# TRV_CC110x_V0_2.net
KiCad netlist of a schematic drawn in EAGLE
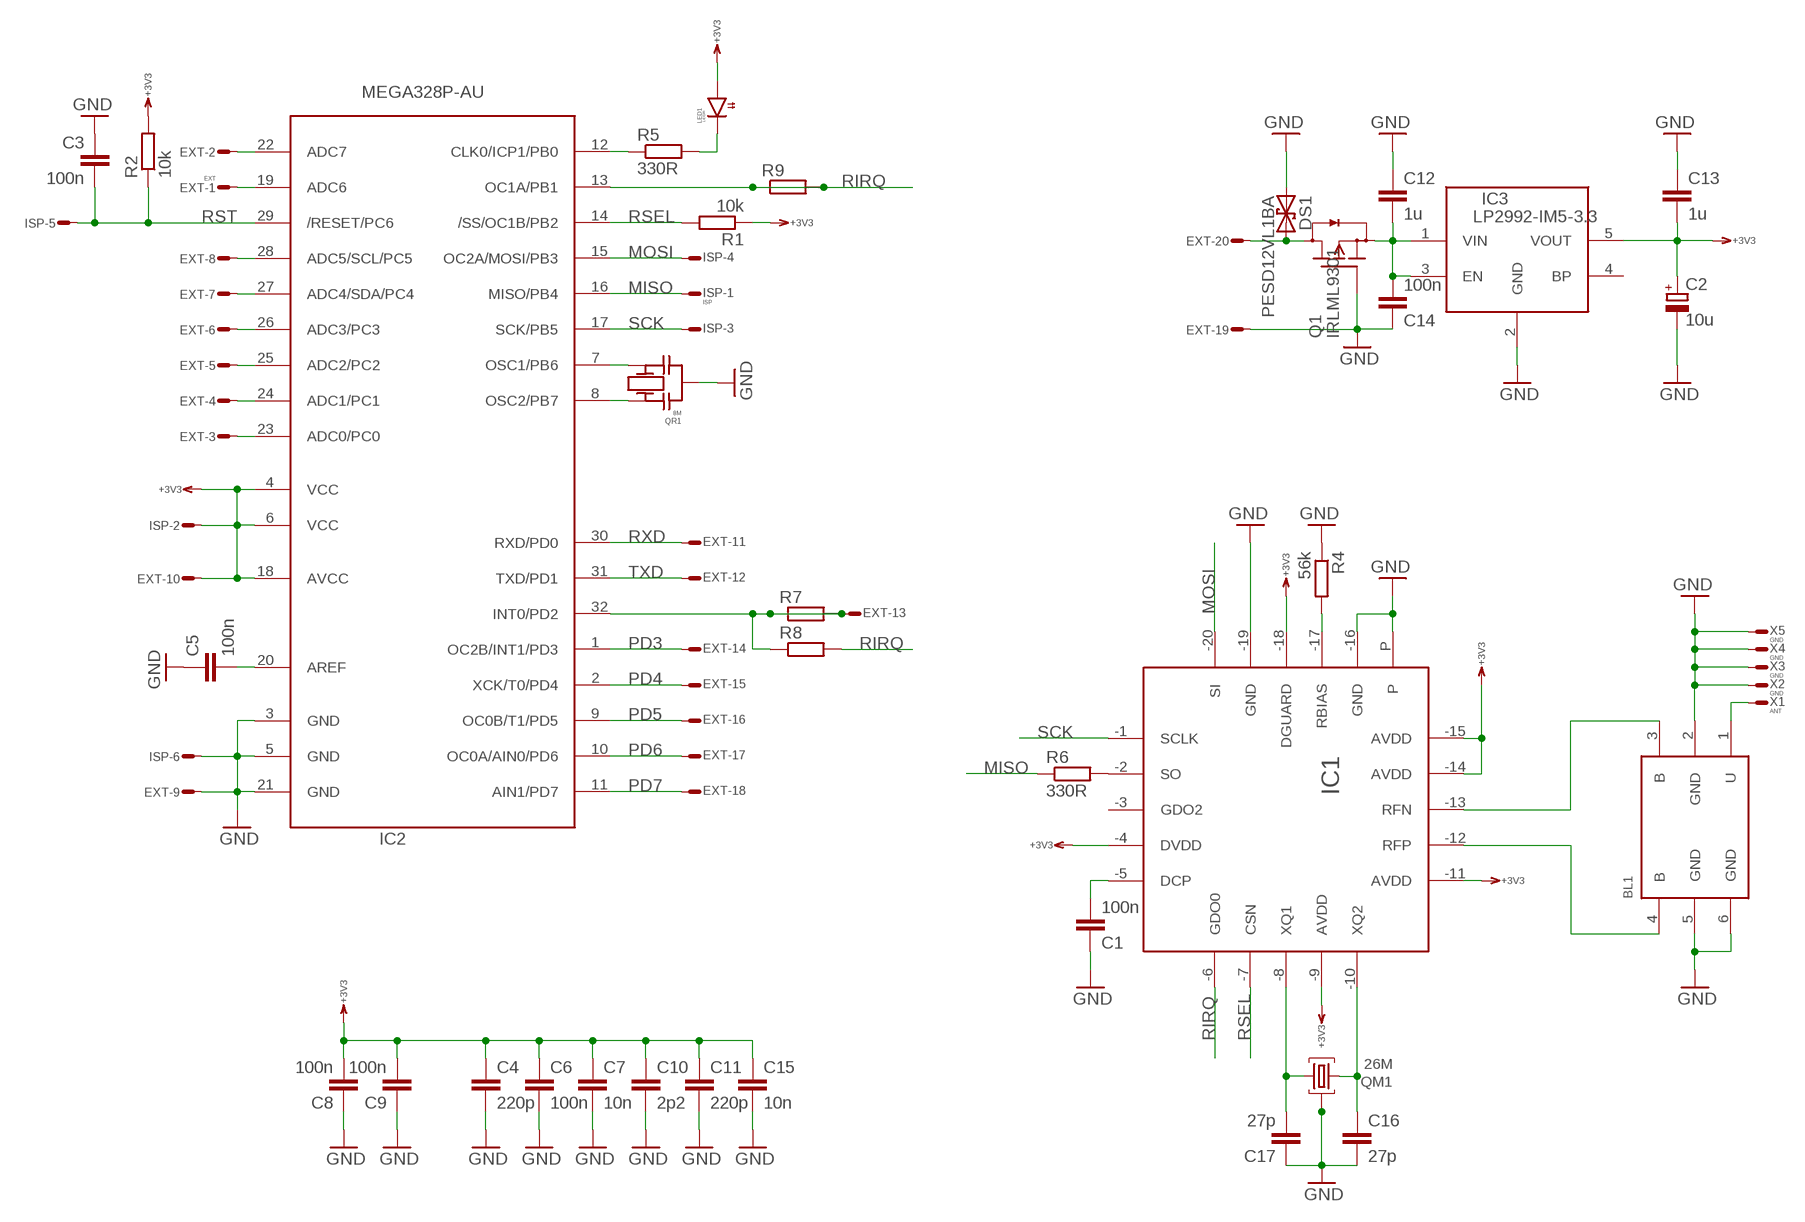
[diagram p0: schematic, sheet 1]

(export (version "E")
  (design (tool "Eeschema 10.0.6"))
  (components
    (comp (ref "BL1") (value "BL") (footprint "eagle-import:BL") (libsource (lib "eagle-import") (part "BL")))
    (comp (ref "C1")
      (value "100n")
      (footprint "eagle-import:0402")
      (libsource (lib "eagle-import") (part "C0402"))
    )
    (comp (ref "C2")
      (value "10u")
      (footprint "eagle-import:SMC_B")
      (libsource (lib "eagle-import") (part "C_POLSMCB"))
    )
    (comp (ref "C3")
      (value "100n")
      (footprint "eagle-import:0603")
      (libsource (lib "eagle-import") (part "C0603"))
    )
    (comp (ref "C4")
      (value "220p")
      (footprint "eagle-import:0402")
      (libsource (lib "eagle-import") (part "C0402"))
    )
    (comp (ref "C5")
      (value "100n")
      (footprint "eagle-import:0603")
      (libsource (lib "eagle-import") (part "C0603"))
    )
    (comp (ref "C6")
      (value "100n")
      (footprint "eagle-import:0402")
      (libsource (lib "eagle-import") (part "C0402"))
    )
    (comp (ref "C7")
      (value "10n")
      (footprint "eagle-import:0402")
      (libsource (lib "eagle-import") (part "C0402"))
    )
    (comp (ref "C8")
      (value "100n")
      (footprint "eagle-import:0603")
      (libsource (lib "eagle-import") (part "C0603"))
    )
    (comp (ref "C9")
      (value "100n")
      (footprint "eagle-import:0603")
      (libsource (lib "eagle-import") (part "C0603"))
    )
    (comp (ref "C10")
      (value "2p2")
      (footprint "eagle-import:0402")
      (libsource (lib "eagle-import") (part "C0402"))
    )
    (comp (ref "C11")
      (value "220p")
      (footprint "eagle-import:0402")
      (libsource (lib "eagle-import") (part "C0402"))
    )
    (comp (ref "C12")
      (value "1u")
      (footprint "eagle-import:0603")
      (libsource (lib "eagle-import") (part "C0603"))
    )
    (comp (ref "C13")
      (value "1u")
      (footprint "eagle-import:0603")
      (libsource (lib "eagle-import") (part "C0603"))
    )
    (comp (ref "C14")
      (value "100n")
      (footprint "eagle-import:0603")
      (libsource (lib "eagle-import") (part "C0603"))
    )
    (comp (ref "C15")
      (value "10n")
      (footprint "eagle-import:0402")
      (libsource (lib "eagle-import") (part "C0402"))
    )
    (comp (ref "C16")
      (value "27p")
      (footprint "eagle-import:0402")
      (libsource (lib "eagle-import") (part "C0402"))
    )
    (comp (ref "C17")
      (value "27p")
      (footprint "eagle-import:0402")
      (libsource (lib "eagle-import") (part "C0402"))
    )
    (comp (ref "DS1")
      (value "PESD12VL1BA")
      (footprint "eagle-import:SOD323")
      (libsource (lib "eagle-import") (part "TVS-U323"))
    )
    (comp (ref "EXT")
      (value "EXT")
      (footprint "eagle-import:ML20S")
      (libsource (lib "eagle-import") (part "ML20?ES"))
    )
    (comp (ref "IC1")
      (value "CC110L")
      (footprint "eagle-import:VQFN20")
      (libsource (lib "eagle-import") (part "CC110L"))
    )
    (comp (ref "IC2")
      (value "MEGA328P-AU")
      (footprint "eagle-import:TQFP32-08")
      (libsource (lib "eagle-import") (part "MEGA168PA"))
    )
    (comp (ref "IC3")
      (value "LP2992-IM5-3.3")
      (footprint "eagle-import:SOT23-5")
      (libsource (lib "eagle-import") (part "LDO"))
    )
    (comp (ref "ISP")
      (value "ISP")
      (footprint "eagle-import:ML6S")
      (libsource (lib "eagle-import") (part "ML6ES"))
    )
    (comp (ref "LED1")
      (value "LEDR")
      (footprint "eagle-import:0805")
      (libsource (lib "eagle-import") (part "LED0805"))
    )
    (comp (ref "Q1")
      (value "IRLML9301")
      (footprint "eagle-import:SOT23")
      (libsource (lib "eagle-import") (part "FET-PDSOT23"))
    )
    (comp (ref "QM1")
      (value "26M")
      (footprint "eagle-import:SMD_4P_3.2X2.5")
      (libsource (lib "eagle-import") (part "QM3.2X2.5"))
    )
    (comp (ref "QR1")
      (value "8M")
      (footprint "eagle-import:CR")
      (libsource (lib "eagle-import") (part "QRCR"))
    )
    (comp (ref "R1")
      (value "10k")
      (footprint "eagle-import:0402")
      (libsource (lib "eagle-import") (part "R0402"))
    )
    (comp (ref "R2")
      (value "10k")
      (footprint "eagle-import:0603")
      (libsource (lib "eagle-import") (part "R0603"))
    )
    (comp (ref "R4")
      (value "56k")
      (footprint "eagle-import:0402")
      (libsource (lib "eagle-import") (part "R0402"))
    )
    (comp (ref "R5")
      (value "330R")
      (footprint "eagle-import:0603")
      (libsource (lib "eagle-import") (part "R0603"))
    )
    (comp (ref "R6")
      (value "330R")
      (footprint "eagle-import:0402")
      (libsource (lib "eagle-import") (part "R0402"))
    )
    (comp (ref "R7")
      (value "R0402")
      (footprint "eagle-import:0402")
      (libsource (lib "eagle-import") (part "R0402"))
    )
    (comp (ref "R8")
      (value "R0402")
      (footprint "eagle-import:0402")
      (libsource (lib "eagle-import") (part "R0402"))
    )
    (comp (ref "R9")
      (value "R0402")
      (footprint "eagle-import:0402")
      (libsource (lib "eagle-import") (part "R0402"))
    )
    (comp (ref "X1")
      (value "ANT")
      (footprint "eagle-import:S2.54_1.27")
      (libsource (lib "eagle-import") (part "WIREPADS2.54/1.27"))
    )
    (comp (ref "X2")
      (value "GND")
      (footprint "eagle-import:S2.54_1.27")
      (libsource (lib "eagle-import") (part "WIREPADS2.54/1.27"))
    )
    (comp (ref "X3")
      (value "GND")
      (footprint "eagle-import:S2.54_1.27")
      (libsource (lib "eagle-import") (part "WIREPADS2.54/1.27"))
    )
    (comp (ref "X4")
      (value "GND")
      (footprint "eagle-import:S2.54_1.27")
      (libsource (lib "eagle-import") (part "WIREPADS2.54/1.27"))
    )
    (comp (ref "X5")
      (value "GND")
      (footprint "eagle-import:S2.54_1.27")
      (libsource (lib "eagle-import") (part "WIREPADS2.54/1.27"))
    )
  )
  (nets
    (net (code "1") (name "+3V3") (class "Default")
      (node (ref "C10") (pin "1") (pinfunction "1_1") (pintype "passive"))
      (node (ref "C11") (pin "1") (pinfunction "1_1") (pintype "passive"))
      (node (ref "C13") (pin "2") (pinfunction "2_2") (pintype "passive"))
      (node (ref "C15") (pin "1") (pinfunction "1_1") (pintype "passive"))
      (node (ref "C2") (pin "+") (pinfunction "+_+") (pintype "passive"))
      (node (ref "C4") (pin "1") (pinfunction "1_1") (pintype "passive"))
      (node (ref "C6") (pin "1") (pinfunction "1_1") (pintype "passive"))
      (node (ref "C7") (pin "1") (pinfunction "1_1") (pintype "passive"))
      (node (ref "C8") (pin "2") (pinfunction "2_2") (pintype "passive"))
      (node (ref "C9") (pin "2") (pinfunction "2_2") (pintype "passive"))
      (node (ref "EXT") (pin "10") (pinfunction "S_10") (pintype "passive"))
      (node (ref "IC1") (pin "-11") (pinfunction "AVDD_-11") (pintype "bidirectional"))
      (node (ref "IC1") (pin "-14") (pinfunction "AVDD_-14") (pintype "bidirectional"))
      (node (ref "IC1") (pin "-15") (pinfunction "AVDD_-15") (pintype "bidirectional"))
      (node (ref "IC1") (pin "-18") (pinfunction "DGUARD_-18") (pintype "bidirectional"))
      (node (ref "IC1") (pin "-4") (pinfunction "DVDD_-4") (pintype "bidirectional"))
      (node (ref "IC1") (pin "-9") (pinfunction "AVDD_-9") (pintype "bidirectional"))
      (node (ref "IC2") (pin "18") (pinfunction "AVCC_18") (pintype "bidirectional"))
      (node (ref "IC2") (pin "4") (pinfunction "VCC_4") (pintype "bidirectional"))
      (node (ref "IC2") (pin "6") (pinfunction "VCC_6") (pintype "bidirectional"))
      (node (ref "IC3") (pin "5") (pinfunction "VOUT_5") (pintype "bidirectional"))
      (node (ref "ISP") (pin "2") (pinfunction "S_2") (pintype "passive"))
      (node (ref "LED1") (pin "C") (pinfunction "A_C") (pintype "bidirectional"))
      (node (ref "R1") (pin "1") (pinfunction "1_1") (pintype "passive"))
      (node (ref "R2") (pin "2") (pinfunction "2_2") (pintype "passive"))
    )
    (net (code "2") (name "/MISO") (class "Default")
      (node (ref "IC2") (pin "16") (pinfunction "MISO/PB4_16") (pintype "bidirectional"))
      (node (ref "ISP") (pin "1") (pinfunction "S_1") (pintype "passive"))
      (node (ref "R6") (pin "1") (pinfunction "1_1") (pintype "passive"))
    )
    (net (code "3") (name "/MOSI") (class "Default")
      (node (ref "IC1") (pin "-20") (pinfunction "SI_-20") (pintype "input"))
      (node (ref "IC2") (pin "15") (pinfunction "OC2A/MOSI/PB3_15") (pintype "bidirectional"))
      (node (ref "ISP") (pin "4") (pinfunction "S_4") (pintype "passive"))
    )
    (net (code "4") (name "/PD3") (class "Default")
      (node (ref "EXT") (pin "14") (pinfunction "S_14") (pintype "passive"))
      (node (ref "IC2") (pin "1") (pinfunction "OC2B/INT1/PD3_1") (pintype "bidirectional"))
    )
    (net (code "5") (name "/PD4") (class "Default")
      (node (ref "EXT") (pin "15") (pinfunction "S_15") (pintype "passive"))
      (node (ref "IC2") (pin "2") (pinfunction "XCK/T0/PD4_2") (pintype "bidirectional"))
    )
    (net (code "6") (name "/PD5") (class "Default")
      (node (ref "EXT") (pin "16") (pinfunction "S_16") (pintype "passive"))
      (node (ref "IC2") (pin "9") (pinfunction "OC0B/T1/PD5_9") (pintype "bidirectional"))
    )
    (net (code "7") (name "/PD6") (class "Default")
      (node (ref "EXT") (pin "17") (pinfunction "S_17") (pintype "passive"))
      (node (ref "IC2") (pin "10") (pinfunction "OC0A/AIN0/PD6_10") (pintype "bidirectional"))
    )
    (net (code "8") (name "/PD7") (class "Default")
      (node (ref "EXT") (pin "18") (pinfunction "S_18") (pintype "passive"))
      (node (ref "IC2") (pin "11") (pinfunction "AIN1/PD7_11") (pintype "bidirectional"))
    )
    (net (code "9") (name "/RIRQ") (class "Default")
      (node (ref "IC1") (pin "-6") (pinfunction "GDO0_-6") (pintype "bidirectional"))
      (node (ref "IC2") (pin "13") (pinfunction "OC1A/PB1_13") (pintype "bidirectional"))
      (node (ref "R8") (pin "2") (pinfunction "2_2") (pintype "passive"))
      (node (ref "R9") (pin "1") (pinfunction "1_1") (pintype "passive"))
      (node (ref "R9") (pin "2") (pinfunction "2_2") (pintype "passive"))
    )
    (net (code "10") (name "/RSEL") (class "Default")
      (node (ref "IC1") (pin "-7") (pinfunction "CSN_-7") (pintype "input"))
      (node (ref "IC2") (pin "14") (pinfunction "/SS/OC1B/PB2_14") (pintype "bidirectional"))
      (node (ref "R1") (pin "2") (pinfunction "2_2") (pintype "passive"))
    )
    (net (code "11") (name "/RST") (class "Default")
      (node (ref "C3") (pin "2") (pinfunction "2_2") (pintype "passive"))
      (node (ref "IC2") (pin "29") (pinfunction "/RESET/PC6_29") (pintype "bidirectional"))
      (node (ref "ISP") (pin "5") (pinfunction "S_5") (pintype "passive"))
      (node (ref "R2") (pin "1") (pinfunction "1_1") (pintype "passive"))
    )
    (net (code "12") (name "/RXD") (class "Default")
      (node (ref "EXT") (pin "11") (pinfunction "S_11") (pintype "passive"))
      (node (ref "IC2") (pin "30") (pinfunction "RXD/PD0_30") (pintype "bidirectional"))
    )
    (net (code "13") (name "/SCK") (class "Default")
      (node (ref "IC1") (pin "-1") (pinfunction "SCLK_-1") (pintype "input"))
      (node (ref "IC2") (pin "17") (pinfunction "SCK/PB5_17") (pintype "bidirectional"))
      (node (ref "ISP") (pin "3") (pinfunction "S_3") (pintype "passive"))
    )
    (net (code "14") (name "/TXD") (class "Default")
      (node (ref "EXT") (pin "12") (pinfunction "S_12") (pintype "passive"))
      (node (ref "IC2") (pin "31") (pinfunction "TXD/PD1_31") (pintype "bidirectional"))
    )
    (net (code "15") (name "GND") (class "Default")
      (node (ref "BL1") (pin "2") (pinfunction "GND_2") (pintype "bidirectional"))
      (node (ref "BL1") (pin "5") (pinfunction "GND_5") (pintype "bidirectional"))
      (node (ref "BL1") (pin "6") (pinfunction "GND_6") (pintype "bidirectional"))
      (node (ref "C1") (pin "1") (pinfunction "1_1") (pintype "passive"))
      (node (ref "C10") (pin "2") (pinfunction "2_2") (pintype "passive"))
      (node (ref "C11") (pin "2") (pinfunction "2_2") (pintype "passive"))
      (node (ref "C12") (pin "1") (pinfunction "1_1") (pintype "passive"))
      (node (ref "C13") (pin "1") (pinfunction "1_1") (pintype "passive"))
      (node (ref "C14") (pin "1") (pinfunction "1_1") (pintype "passive"))
      (node (ref "C15") (pin "2") (pinfunction "2_2") (pintype "passive"))
      (node (ref "C16") (pin "2") (pinfunction "2_2") (pintype "passive"))
      (node (ref "C17") (pin "1") (pinfunction "1_1") (pintype "passive"))
      (node (ref "C2") (pin "-") (pinfunction "-_-") (pintype "passive"))
      (node (ref "C3") (pin "1") (pinfunction "1_1") (pintype "passive"))
      (node (ref "C4") (pin "2") (pinfunction "2_2") (pintype "passive"))
      (node (ref "C5") (pin "1") (pinfunction "1_1") (pintype "passive"))
      (node (ref "C6") (pin "2") (pinfunction "2_2") (pintype "passive"))
      (node (ref "C7") (pin "2") (pinfunction "2_2") (pintype "passive"))
      (node (ref "C8") (pin "1") (pinfunction "1_1") (pintype "passive"))
      (node (ref "C9") (pin "1") (pinfunction "1_1") (pintype "passive"))
      (node (ref "DS1") (pin "A") (pinfunction "1_A") (pintype "passive"))
      (node (ref "EXT") (pin "19") (pinfunction "S_19") (pintype "passive"))
      (node (ref "EXT") (pin "9") (pinfunction "S_9") (pintype "passive"))
      (node (ref "IC1") (pin "-16") (pinfunction "GND_-16") (pintype "bidirectional"))
      (node (ref "IC1") (pin "-19") (pinfunction "GND_-19") (pintype "bidirectional"))
      (node (ref "IC1") (pin "P") (pinfunction "P_P") (pintype "bidirectional"))
      (node (ref "IC2") (pin "21") (pinfunction "GND_21") (pintype "bidirectional"))
      (node (ref "IC2") (pin "3") (pinfunction "GND_3") (pintype "bidirectional"))
      (node (ref "IC2") (pin "5") (pinfunction "GND_5") (pintype "bidirectional"))
      (node (ref "IC3") (pin "2") (pinfunction "GND_2") (pintype "bidirectional"))
      (node (ref "ISP") (pin "6") (pinfunction "S_6") (pintype "passive"))
      (node (ref "Q1") (pin "1") (pinfunction "G_1") (pintype "passive"))
      (node (ref "QM1") (pin "2") (pinfunction "M1_2") (pintype "passive"))
      (node (ref "QM1") (pin "4") (pinfunction "M2_4") (pintype "passive"))
      (node (ref "QR1") (pin "M") (pinfunction "M_M") (pintype "passive"))
      (node (ref "R4") (pin "1") (pinfunction "1_1") (pintype "passive"))
      (node (ref "X2") (pin "1") (pinfunction "S_1") (pintype "passive"))
      (node (ref "X3") (pin "1") (pinfunction "S_1") (pintype "passive"))
      (node (ref "X4") (pin "1") (pinfunction "S_1") (pintype "passive"))
      (node (ref "X5") (pin "1") (pinfunction "S_1") (pintype "passive"))
    )
    (net (code "16") (name "Net-(BL1-U)") (class "Default")
      (node (ref "BL1") (pin "1") (pinfunction "U_1") (pintype "bidirectional"))
      (node (ref "X1") (pin "1") (pinfunction "S_1") (pintype "passive"))
    )
    (net (code "17") (name "Net-(DS1-2)") (class "Default")
      (node (ref "DS1") (pin "C") (pinfunction "2_C") (pintype "passive"))
      (node (ref "EXT") (pin "20") (pinfunction "S_20") (pintype "passive"))
      (node (ref "Q1") (pin "3") (pinfunction "D_3") (pintype "passive"))
    )
    (net (code "18") (name "Net-(EXTA-S)") (class "Default")
      (node (ref "EXT") (pin "1") (pinfunction "S_1") (pintype "passive"))
      (node (ref "IC2") (pin "19") (pinfunction "ADC6_19") (pintype "bidirectional"))
    )
    (net (code "19") (name "Net-(EXTE-S)") (class "Default")
      (node (ref "EXT") (pin "13") (pinfunction "S_13") (pintype "passive"))
      (node (ref "IC2") (pin "32") (pinfunction "INT0/PD2_32") (pintype "bidirectional"))
      (node (ref "R7") (pin "1") (pinfunction "1_1") (pintype "passive"))
      (node (ref "R7") (pin "2") (pinfunction "2_2") (pintype "passive"))
      (node (ref "R8") (pin "1") (pinfunction "1_1") (pintype "passive"))
    )
    (net (code "20") (name "Net-(EXTL-S)") (class "Default")
      (node (ref "EXT") (pin "2") (pinfunction "S_2") (pintype "passive"))
      (node (ref "IC2") (pin "22") (pinfunction "ADC7_22") (pintype "bidirectional"))
    )
    (net (code "21") (name "Net-(EXTN-S)") (class "Default")
      (node (ref "EXT") (pin "3") (pinfunction "S_3") (pintype "passive"))
      (node (ref "IC2") (pin "23") (pinfunction "ADC0/PC0_23") (pintype "bidirectional"))
    )
    (net (code "22") (name "Net-(EXTO-S)") (class "Default")
      (node (ref "EXT") (pin "4") (pinfunction "S_4") (pintype "passive"))
      (node (ref "IC2") (pin "24") (pinfunction "ADC1/PC1_24") (pintype "bidirectional"))
    )
    (net (code "23") (name "Net-(EXTP-S)") (class "Default")
      (node (ref "EXT") (pin "5") (pinfunction "S_5") (pintype "passive"))
      (node (ref "IC2") (pin "25") (pinfunction "ADC2/PC2_25") (pintype "bidirectional"))
    )
    (net (code "24") (name "Net-(EXTQ-S)") (class "Default")
      (node (ref "EXT") (pin "6") (pinfunction "S_6") (pintype "passive"))
      (node (ref "IC2") (pin "26") (pinfunction "ADC3/PC3_26") (pintype "bidirectional"))
    )
    (net (code "25") (name "Net-(EXTR-S)") (class "Default")
      (node (ref "EXT") (pin "7") (pinfunction "S_7") (pintype "passive"))
      (node (ref "IC2") (pin "27") (pinfunction "ADC4/SDA/PC4_27") (pintype "bidirectional"))
    )
    (net (code "26") (name "Net-(EXTS-S)") (class "Default")
      (node (ref "EXT") (pin "8") (pinfunction "S_8") (pintype "passive"))
      (node (ref "IC2") (pin "28") (pinfunction "ADC5/SCL/PC5_28") (pintype "bidirectional"))
    )
    (net (code "27") (name "Net-(IC1-DCP)") (class "Default")
      (node (ref "C1") (pin "2") (pinfunction "2_2") (pintype "passive"))
      (node (ref "IC1") (pin "-5") (pinfunction "DCP_-5") (pintype "bidirectional"))
    )
    (net (code "28") (name "Net-(IC1-RBIAS)") (class "Default")
      (node (ref "IC1") (pin "-17") (pinfunction "RBIAS_-17") (pintype "bidirectional"))
      (node (ref "R4") (pin "2") (pinfunction "2_2") (pintype "passive"))
    )
    (net (code "29") (name "Net-(IC1-RFN)") (class "Default")
      (node (ref "BL1") (pin "3") (pinfunction "B_3") (pintype "bidirectional"))
      (node (ref "IC1") (pin "-13") (pinfunction "RFN_-13") (pintype "bidirectional"))
    )
    (net (code "30") (name "Net-(IC1-RFP)") (class "Default")
      (node (ref "BL1") (pin "4") (pinfunction "B_4") (pintype "bidirectional"))
      (node (ref "IC1") (pin "-12") (pinfunction "RFP_-12") (pintype "bidirectional"))
    )
    (net (code "31") (name "Net-(IC1-SO)") (class "Default")
      (node (ref "IC1") (pin "-2") (pinfunction "SO_-2") (pintype "output"))
      (node (ref "R6") (pin "2") (pinfunction "2_2") (pintype "passive"))
    )
    (net (code "32") (name "Net-(IC1-XQ1)") (class "Default")
      (node (ref "C17") (pin "2") (pinfunction "2_2") (pintype "passive"))
      (node (ref "IC1") (pin "-8") (pinfunction "XQ1_-8") (pintype "bidirectional"))
      (node (ref "QM1") (pin "3") (pinfunction "2_3") (pintype "passive"))
    )
    (net (code "33") (name "Net-(IC1-XQ2)") (class "Default")
      (node (ref "C16") (pin "1") (pinfunction "1_1") (pintype "passive"))
      (node (ref "IC1") (pin "-10") (pinfunction "XQ2_-10") (pintype "bidirectional"))
      (node (ref "QM1") (pin "1") (pinfunction "1_1") (pintype "passive"))
    )
    (net (code "34") (name "Net-(IC2-AREF)") (class "Default")
      (node (ref "C5") (pin "2") (pinfunction "2_2") (pintype "passive"))
      (node (ref "IC2") (pin "20") (pinfunction "AREF_20") (pintype "bidirectional"))
    )
    (net (code "35") (name "Net-(IC2-CLK0{slash}ICP1{slash}PB0)") (class "Default")
      (node (ref "IC2") (pin "12") (pinfunction "CLK0/ICP1/PB0_12") (pintype "bidirectional"))
      (node (ref "R5") (pin "1") (pinfunction "1_1") (pintype "passive"))
    )
    (net (code "36") (name "Net-(IC2-OSC1{slash}PB6)") (class "Default")
      (node (ref "IC2") (pin "7") (pinfunction "OSC1/PB6_7") (pintype "bidirectional"))
      (node (ref "QR1") (pin "2") (pinfunction "2_2") (pintype "passive"))
    )
    (net (code "37") (name "Net-(IC2-OSC2{slash}PB7)") (class "Default")
      (node (ref "IC2") (pin "8") (pinfunction "OSC2/PB7_8") (pintype "bidirectional"))
      (node (ref "QR1") (pin "1") (pinfunction "1_1") (pintype "passive"))
    )
    (net (code "38") (name "Net-(IC3-EN)") (class "Default")
      (node (ref "C12") (pin "2") (pinfunction "2_2") (pintype "passive"))
      (node (ref "C14") (pin "2") (pinfunction "2_2") (pintype "passive"))
      (node (ref "IC3") (pin "1") (pinfunction "VIN_1") (pintype "bidirectional"))
      (node (ref "IC3") (pin "3") (pinfunction "EN_3") (pintype "bidirectional"))
      (node (ref "Q1") (pin "2") (pinfunction "S_2") (pintype "passive"))
    )
    (net (code "39") (name "Net-(LED1-C)") (class "Default")
      (node (ref "LED1") (pin "A") (pinfunction "C_A") (pintype "bidirectional"))
      (node (ref "R5") (pin "2") (pinfunction "2_2") (pintype "passive"))
    )
    (net (code "40") (name "unconnected-(IC1-GDO2-Pad-3)") (class "Default")
      (node (ref "IC1") (pin "-3") (pinfunction "GDO2_-3") (pintype "output"))
    )
    (net (code "41") (name "unconnected-(IC3-BP-Pad4)") (class "Default")
      (node (ref "IC3") (pin "4") (pinfunction "BP_4") (pintype "bidirectional"))
    )
  )
)
